# SMD.net
KiCad netlist of a schematic drawn in EAGLE
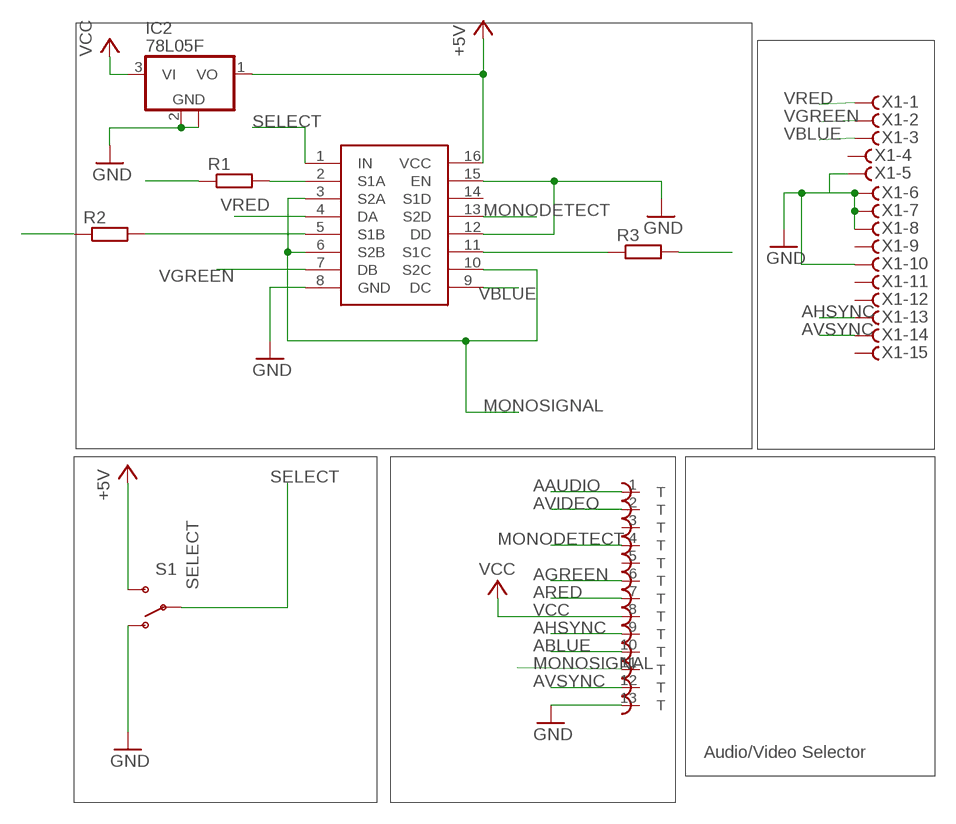
[diagram p0: schematic, sheet 1]

(export (version "E")
  (design (tool "Eeschema 10.0.6"))
  (components
    (comp (ref "ATARIOUT")
      (value "DIN13T")
      (footprint "eagle-import:ADADS")
      (libsource (lib "eagle-import") (part "DIN13T"))
    )
    (comp (ref "IC2")
      (value "78L05F")
      (footprint "eagle-import:SOT89")
      (libsource (lib "eagle-import") (part "78LF05"))
    )
    (comp (ref "R1")
      (value "R-EU_R1206")
      (footprint "eagle-import:R1206")
      (libsource (lib "eagle-import") (part "R-EU_R1206"))
    )
    (comp (ref "R2")
      (value "R-EU_R1206")
      (footprint "eagle-import:R1206")
      (libsource (lib "eagle-import") (part "R-EU_R1206"))
    )
    (comp (ref "R3")
      (value "R-EU_R1206")
      (footprint "eagle-import:R1206")
      (libsource (lib "eagle-import") (part "R-EU_R1206"))
    )
    (comp (ref "S1")
      (value "SWITCH-SPDT-SMD-A")
      (footprint "eagle-import:SWITCH-SPST-SMD-A")
      (libsource (lib "eagle-import") (part "SWITCH-SPDT-SMD-A"))
    )
    (comp (ref "TS5V330")
      (value "V330")
      (footprint "eagle-import:SOIC16N")
      (libsource (lib "eagle-import") (part "V330"))
    )
    (comp (ref "X1")
      (value "F15HDVS")
      (footprint "eagle-import:HDF15V")
      (libsource (lib "eagle-import") (part "F15?SHDV"))
    )
  )
  (nets
    (net (code "1") (name "+5V") (class "Default")
      (node (ref "IC2") (pin "1") (pinfunction "VO_1") (pintype "passive"))
      (node (ref "S1") (pin "3") (pinfunction "S_3") (pintype "passive"))
      (node (ref "TS5V330") (pin "16") (pinfunction "VCC_16") (pintype "bidirectional"))
    )
    (net (code "2") (name "/AAUDIO") (class "Default")
      (node (ref "ATARIOUT") (pin "1") (pinfunction "T_1") (pintype "passive"))
    )
    (net (code "3") (name "/ABLUE") (class "Default")
      (node (ref "ATARIOUT") (pin "10") (pinfunction "T_10") (pintype "passive"))
      (node (ref "R3") (pin "2") (pinfunction "2_2") (pintype "passive"))
    )
    (net (code "4") (name "/AGREEN") (class "Default")
      (node (ref "ATARIOUT") (pin "6") (pinfunction "T_6") (pintype "passive"))
      (node (ref "R2") (pin "1") (pinfunction "1_1") (pintype "passive"))
    )
    (net (code "5") (name "/AHSYNC") (class "Default")
      (node (ref "ATARIOUT") (pin "9") (pinfunction "T_9") (pintype "passive"))
      (node (ref "X1") (pin "13") (pinfunction "F_13") (pintype "passive"))
    )
    (net (code "6") (name "/ARED") (class "Default")
      (node (ref "ATARIOUT") (pin "7") (pinfunction "T_7") (pintype "passive"))
      (node (ref "R1") (pin "1") (pinfunction "1_1") (pintype "passive"))
    )
    (net (code "7") (name "/AVIDEO") (class "Default")
      (node (ref "ATARIOUT") (pin "2") (pinfunction "T_2") (pintype "passive"))
    )
    (net (code "8") (name "/AVSYNC") (class "Default")
      (node (ref "ATARIOUT") (pin "12") (pinfunction "T_12") (pintype "passive"))
      (node (ref "X1") (pin "14") (pinfunction "F_14") (pintype "passive"))
    )
    (net (code "9") (name "/MONODETECT") (class "Default")
      (node (ref "ATARIOUT") (pin "4") (pinfunction "T_4") (pintype "passive"))
      (node (ref "TS5V330") (pin "13") (pinfunction "S2D_13") (pintype "bidirectional"))
    )
    (net (code "10") (name "/MONOSIGNAL") (class "Default")
      (node (ref "ATARIOUT") (pin "11") (pinfunction "T_11") (pintype "passive"))
      (node (ref "TS5V330") (pin "10") (pinfunction "S2C_10") (pintype "bidirectional"))
      (node (ref "TS5V330") (pin "3") (pinfunction "S2A_3") (pintype "bidirectional"))
      (node (ref "TS5V330") (pin "6") (pinfunction "S2B_6") (pintype "bidirectional"))
    )
    (net (code "11") (name "/SELECT") (class "Default")
      (node (ref "S1") (pin "2") (pinfunction "P_2") (pintype "passive"))
      (node (ref "TS5V330") (pin "1") (pinfunction "IN_1") (pintype "bidirectional"))
    )
    (net (code "12") (name "/VBLUE") (class "Default")
      (node (ref "TS5V330") (pin "9") (pinfunction "DC_9") (pintype "bidirectional"))
      (node (ref "X1") (pin "3") (pinfunction "F_3") (pintype "passive"))
    )
    (net (code "13") (name "/VGREEN") (class "Default")
      (node (ref "TS5V330") (pin "7") (pinfunction "DB_7") (pintype "bidirectional"))
      (node (ref "X1") (pin "2") (pinfunction "F_2") (pintype "passive"))
    )
    (net (code "14") (name "/VRED") (class "Default")
      (node (ref "TS5V330") (pin "4") (pinfunction "DA_4") (pintype "bidirectional"))
      (node (ref "X1") (pin "1") (pinfunction "F_1") (pintype "passive"))
    )
    (net (code "15") (name "GND") (class "Default")
      (node (ref "ATARIOUT") (pin "13") (pinfunction "T_13") (pintype "passive"))
      (node (ref "IC2") (pin "2") (pinfunction "GND_2") (pintype "passive"))
      (node (ref "IC2") (pin "2@1") (pinfunction "GND_2@1") (pintype "passive"))
      (node (ref "S1") (pin "1") (pinfunction "O_1") (pintype "passive"))
      (node (ref "TS5V330") (pin "12") (pinfunction "DD_12") (pintype "bidirectional"))
      (node (ref "TS5V330") (pin "15") (pinfunction "EN_15") (pintype "bidirectional"))
      (node (ref "TS5V330") (pin "8") (pinfunction "GND_8") (pintype "bidirectional"))
      (node (ref "X1") (pin "10") (pinfunction "F_10") (pintype "passive"))
      (node (ref "X1") (pin "5") (pinfunction "F_5") (pintype "passive"))
      (node (ref "X1") (pin "6") (pinfunction "F_6") (pintype "passive"))
      (node (ref "X1") (pin "7") (pinfunction "F_7") (pintype "passive"))
      (node (ref "X1") (pin "8") (pinfunction "F_8") (pintype "passive"))
    )
    (net (code "16") (name "Net-(TS5V330-S1A)") (class "Default")
      (node (ref "R1") (pin "2") (pinfunction "2_2") (pintype "passive"))
      (node (ref "TS5V330") (pin "2") (pinfunction "S1A_2") (pintype "bidirectional"))
    )
    (net (code "17") (name "Net-(TS5V330-S1B)") (class "Default")
      (node (ref "R2") (pin "2") (pinfunction "2_2") (pintype "passive"))
      (node (ref "TS5V330") (pin "5") (pinfunction "S1B_5") (pintype "bidirectional"))
    )
    (net (code "18") (name "Net-(TS5V330-S1C)") (class "Default")
      (node (ref "R3") (pin "1") (pinfunction "1_1") (pintype "passive"))
      (node (ref "TS5V330") (pin "11") (pinfunction "S1C_11") (pintype "bidirectional"))
    )
    (net (code "19") (name "VCC") (class "Default")
      (node (ref "ATARIOUT") (pin "8") (pinfunction "T_8") (pintype "passive"))
      (node (ref "IC2") (pin "3") (pinfunction "VI_3") (pintype "input"))
    )
    (net (code "20") (name "unconnected-(ATARIOUTG-T-Pad3)") (class "Default")
      (node (ref "ATARIOUT") (pin "3") (pinfunction "T_3") (pintype "passive"))
    )
    (net (code "21") (name "unconnected-(ATARIOUTI-T-Pad5)") (class "Default")
      (node (ref "ATARIOUT") (pin "5") (pinfunction "T_5") (pintype "passive"))
    )
    (net (code "22") (name "unconnected-(TS5V330-S1D-Pad14)") (class "Default")
      (node (ref "TS5V330") (pin "14") (pinfunction "S1D_14") (pintype "bidirectional"))
    )
    (net (code "23") (name "unconnected-(X1C-F-Pad11)") (class "Default")
      (node (ref "X1") (pin "11") (pinfunction "F_11") (pintype "passive"))
    )
    (net (code "24") (name "unconnected-(X1D-F-Pad12)") (class "Default")
      (node (ref "X1") (pin "12") (pinfunction "F_12") (pintype "passive"))
    )
    (net (code "25") (name "unconnected-(X1G-F-Pad15)") (class "Default")
      (node (ref "X1") (pin "15") (pinfunction "F_15") (pintype "passive"))
    )
    (net (code "26") (name "unconnected-(X1J-F-Pad4)") (class "Default")
      (node (ref "X1") (pin "4") (pinfunction "F_4") (pintype "passive"))
    )
    (net (code "27") (name "unconnected-(X1O-F-Pad9)") (class "Default")
      (node (ref "X1") (pin "9") (pinfunction "F_9") (pintype "passive"))
    )
  )
)
